# ScaleSimulator_Test.net
KiCad netlist of a schematic drawn in Altium Designer
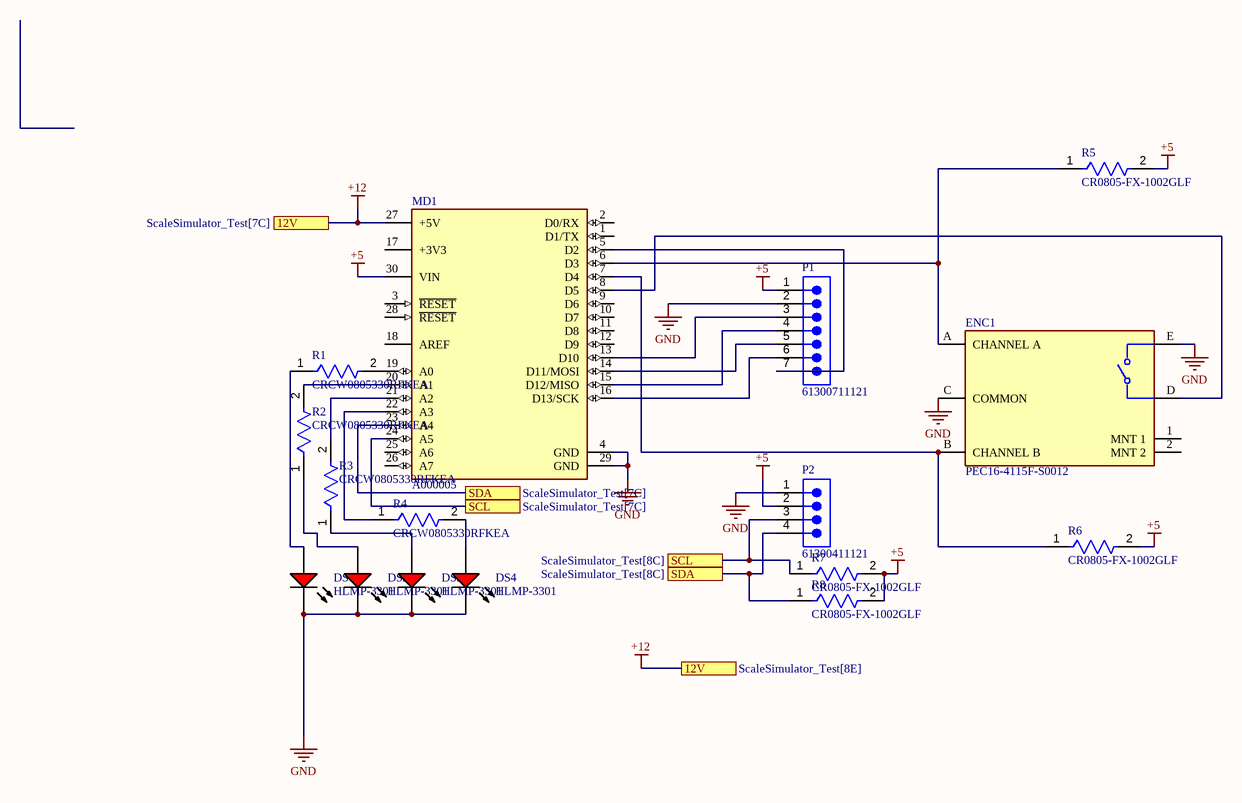
[diagram p0: ScaleSimulator_Test.SchDoc]

(export (version "E")
  (design (tool "Eeschema 10.0.6"))
  (components
    (comp (ref "DS1")
      (value "HLMP-3301")
      (footprint "AVAG-HLMP-3301-2")
      (description "T-1 3/4 (5 mm) Diffused LED Lamp, 1.9 V, -40 to 100 degC, 2-Pin THD, RoHS, Bulk")
      (fields (field (name "MANUFACTURER") "Avago"))
      (libsource (lib "Altium Content Vault") (part "LED-RED-K1A2-2"))
    )
    (comp (ref "DS2")
      (value "HLMP-3301")
      (footprint "AVAG-HLMP-3301-2")
      (description "T-1 3/4 (5 mm) Diffused LED Lamp, 1.9 V, -40 to 100 degC, 2-Pin THD, RoHS, Bulk")
      (fields (field (name "MANUFACTURER") "Avago"))
      (libsource (lib "Altium Content Vault") (part "LED-RED-K1A2-2"))
    )
    (comp (ref "DS3")
      (value "HLMP-3301")
      (footprint "AVAG-HLMP-3301-2")
      (description "T-1 3/4 (5 mm) Diffused LED Lamp, 1.9 V, -40 to 100 degC, 2-Pin THD, RoHS, Bulk")
      (fields (field (name "MANUFACTURER") "Avago"))
      (libsource (lib "Altium Content Vault") (part "LED-RED-K1A2-2"))
    )
    (comp (ref "DS4")
      (value "HLMP-3301")
      (footprint "AVAG-HLMP-3301-2")
      (description "T-1 3/4 (5 mm) Diffused LED Lamp, 1.9 V, -40 to 100 degC, 2-Pin THD, RoHS, Bulk")
      (fields (field (name "MANUFACTURER") "Avago"))
      (libsource (lib "Altium Content Vault") (part "LED-RED-K1A2-2"))
    )
    (comp (ref "ENC1")
      (value "PEC16-4115F-S0012")
      (footprint "FP-PEC16-4115F-S0012-MFG")
      (description "ROTARY ENCODER MECHANICAL 12PPR")
      (libsource (lib "Altium Content Vault") (part "74e6fcc4b0c7d654d48d7f2a48e5514"))
    )
    (comp (ref "MD1")
      (value "A000005")
      (footprint "FP-A000005-MFG")
      (description "ARDUINO NANO ATMEGA328 EVAL BRD")
      (libsource (lib "Altium Content Vault") (part "d190c066e99afd1c6882cf92e11b2cc"))
    )
    (comp (ref "P1")
      (value "61300711121")
      (footprint "61300711121")
      (libsource (lib "Altium Content Vault") (part "Header_Male_1R_07P"))
    )
    (comp (ref "P2")
      (value "61300411121")
      (footprint "61300411121")
      (libsource (lib "Altium Content Vault") (part "Header_Male_1R_04P"))
    )
    (comp (ref "R1")
      (value "CRCW0805330RFKEA")
      (footprint "FP-CRCW0805-e3-MFG")
      (description "RES Thick Film, 330Ω, 1%, 0.125W, 100ppm/°C, 0805")
      (fields (field (name "TOLERANCE") "1%"))
      (libsource (lib "Altium Content Vault") (part "1029c3af85768c4190bb7ad29bc67b5"))
    )
    (comp (ref "R2")
      (value "CRCW0805330RFKEA")
      (footprint "FP-CRCW0805-e3-MFG")
      (description "RES Thick Film, 330Ω, 1%, 0.125W, 100ppm/°C, 0805")
      (fields (field (name "TOLERANCE") "1%"))
      (libsource (lib "Altium Content Vault") (part "1029c3af85768c4190bb7ad29bc67b5"))
    )
    (comp (ref "R3")
      (value "CRCW0805330RFKEA")
      (footprint "FP-CRCW0805-e3-MFG")
      (description "RES Thick Film, 330Ω, 1%, 0.125W, 100ppm/°C, 0805")
      (fields (field (name "TOLERANCE") "1%"))
      (libsource (lib "Altium Content Vault") (part "1029c3af85768c4190bb7ad29bc67b5"))
    )
    (comp (ref "R4")
      (value "CRCW0805330RFKEA")
      (footprint "FP-CRCW0805-e3-MFG")
      (description "RES Thick Film, 330Ω, 1%, 0.125W, 100ppm/°C, 0805")
      (fields (field (name "TOLERANCE") "1%"))
      (libsource (lib "Altium Content Vault") (part "1029c3af85768c4190bb7ad29bc67b5"))
    )
    (comp (ref "R5")
      (value "CR0805-FX-1002GLF")
      (footprint "FP-CR0805-IPC_C")
      (description "Thick Film Chip Resistors 0805 10kΩ 0.125W 1% 100ppm/°C")
      (fields (field (name "TOLERANCE") "1%"))
      (libsource (lib "Altium Content Vault") (part "1029c3af85768c4190bb7ad29bc67b5"))
    )
    (comp (ref "R6")
      (value "CR0805-FX-1002GLF")
      (footprint "FP-CR0805-IPC_C")
      (description "Thick Film Chip Resistors 0805 10kΩ 0.125W 1% 100ppm/°C")
      (fields (field (name "TOLERANCE") "1%"))
      (libsource (lib "Altium Content Vault") (part "1029c3af85768c4190bb7ad29bc67b5"))
    )
    (comp (ref "R7")
      (value "CR0805-FX-1002GLF")
      (footprint "FP-CR0805-IPC_C")
      (description "Thick Film Chip Resistors 0805 10kΩ 0.125W 1% 100ppm/°C")
      (fields (field (name "TOLERANCE") "1%"))
      (libsource (lib "Altium Content Vault") (part "1029c3af85768c4190bb7ad29bc67b5"))
    )
    (comp (ref "R8")
      (value "CR0805-FX-1002GLF")
      (footprint "FP-CR0805-IPC_C")
      (description "Thick Film Chip Resistors 0805 10kΩ 0.125W 1% 100ppm/°C")
      (fields (field (name "TOLERANCE") "1%"))
      (libsource (lib "Altium Content Vault") (part "1029c3af85768c4190bb7ad29bc67b5"))
    )
  )
  (nets
    (net (code "1") (name "+5") (class "Default")
      (node (ref "MD1") (pin "30") (pinfunction "VIN_30") (pintype "power_in"))
      (node (ref "P1") (pin "1") (pinfunction "1_1") (pintype "passive"))
      (node (ref "P2") (pin "2") (pinfunction "2_2") (pintype "passive"))
      (node (ref "R5") (pin "2") (pinfunction "2_2") (pintype "passive"))
      (node (ref "R6") (pin "2") (pinfunction "2_2") (pintype "passive"))
      (node (ref "R7") (pin "2") (pinfunction "2_2") (pintype "passive"))
      (node (ref "R8") (pin "2") (pinfunction "2_2") (pintype "passive"))
    )
    (net (code "2") (name "+12") (class "Default")
      (node (ref "MD1") (pin "27") (pinfunction "+5V_27") (pintype "power_in"))
    )
    (net (code "3") (name "/SCL") (class "Default")
      (node (ref "MD1") (pin "24") (pinfunction "A5_24") (pintype "bidirectional"))
      (node (ref "P2") (pin "3") (pinfunction "3_3") (pintype "passive"))
      (node (ref "R7") (pin "1") (pinfunction "1_1") (pintype "passive"))
    )
    (net (code "4") (name "/SDA") (class "Default")
      (node (ref "MD1") (pin "23") (pinfunction "A4_23") (pintype "bidirectional"))
      (node (ref "P2") (pin "4") (pinfunction "4_4") (pintype "passive"))
      (node (ref "R8") (pin "1") (pinfunction "1_1") (pintype "passive"))
    )
    (net (code "5") (name "GND") (class "Default")
      (node (ref "DS1") (pin "1") (pinfunction "K_1") (pintype "passive"))
      (node (ref "DS2") (pin "1") (pinfunction "K_1") (pintype "passive"))
      (node (ref "DS3") (pin "1") (pinfunction "K_1") (pintype "passive"))
      (node (ref "DS4") (pin "1") (pinfunction "K_1") (pintype "passive"))
      (node (ref "ENC1") (pin "C") (pinfunction "COMMON_C") (pintype "passive"))
      (node (ref "ENC1") (pin "E") (pinfunction "E_E") (pintype "passive"))
      (node (ref "MD1") (pin "29") (pinfunction "GND_29") (pintype "power_in"))
      (node (ref "MD1") (pin "4") (pinfunction "GND_4") (pintype "power_in"))
      (node (ref "P1") (pin "2") (pinfunction "2_2") (pintype "passive"))
      (node (ref "P2") (pin "1") (pinfunction "1_1") (pintype "passive"))
    )
    (net (code "6") (name "Net-(DS1-A)") (class "Default")
      (node (ref "DS1") (pin "2") (pinfunction "A_2") (pintype "passive"))
      (node (ref "R1") (pin "1") (pinfunction "1_1") (pintype "passive"))
    )
    (net (code "7") (name "Net-(DS2-A)") (class "Default")
      (node (ref "DS2") (pin "2") (pinfunction "A_2") (pintype "passive"))
      (node (ref "R2") (pin "1") (pinfunction "1_1") (pintype "passive"))
    )
    (net (code "8") (name "Net-(DS3-A)") (class "Default")
      (node (ref "DS3") (pin "2") (pinfunction "A_2") (pintype "passive"))
      (node (ref "R3") (pin "1") (pinfunction "1_1") (pintype "passive"))
    )
    (net (code "9") (name "Net-(DS4-A)") (class "Default")
      (node (ref "DS4") (pin "2") (pinfunction "A_2") (pintype "passive"))
      (node (ref "R4") (pin "2") (pinfunction "2_2") (pintype "passive"))
    )
    (net (code "10") (name "Net-(ENC1-CHANNEL_A)") (class "Default")
      (node (ref "ENC1") (pin "A") (pinfunction "CHANNEL_A_A") (pintype "passive"))
      (node (ref "MD1") (pin "6") (pinfunction "D3_6") (pintype "bidirectional"))
      (node (ref "R5") (pin "1") (pinfunction "1_1") (pintype "passive"))
    )
    (net (code "11") (name "Net-(ENC1-CHANNEL_B)") (class "Default")
      (node (ref "ENC1") (pin "B") (pinfunction "CHANNEL_B_B") (pintype "passive"))
      (node (ref "MD1") (pin "7") (pinfunction "D4_7") (pintype "bidirectional"))
      (node (ref "R6") (pin "1") (pinfunction "1_1") (pintype "passive"))
    )
    (net (code "12") (name "Net-(MD1-A0)") (class "Default")
      (node (ref "MD1") (pin "19") (pinfunction "A0_19") (pintype "bidirectional"))
      (node (ref "R1") (pin "2") (pinfunction "2_2") (pintype "passive"))
    )
    (net (code "13") (name "Net-(MD1-A1)") (class "Default")
      (node (ref "MD1") (pin "20") (pinfunction "A1_20") (pintype "bidirectional"))
      (node (ref "R2") (pin "2") (pinfunction "2_2") (pintype "passive"))
    )
    (net (code "14") (name "Net-(MD1-A2)") (class "Default")
      (node (ref "MD1") (pin "21") (pinfunction "A2_21") (pintype "bidirectional"))
      (node (ref "R3") (pin "2") (pinfunction "2_2") (pintype "passive"))
    )
    (net (code "15") (name "Net-(MD1-A3)") (class "Default")
      (node (ref "MD1") (pin "22") (pinfunction "A3_22") (pintype "bidirectional"))
      (node (ref "R4") (pin "1") (pinfunction "1_1") (pintype "passive"))
    )
    (net (code "16") (name "Net-(MD1-D2)") (class "Default")
      (node (ref "MD1") (pin "5") (pinfunction "D2_5") (pintype "bidirectional"))
      (node (ref "P1") (pin "7") (pinfunction "7_7") (pintype "passive"))
    )
    (net (code "17") (name "Net-(MD1-D5)") (class "Default")
      (node (ref "ENC1") (pin "D") (pinfunction "D_D") (pintype "passive"))
      (node (ref "MD1") (pin "8") (pinfunction "D5_8") (pintype "bidirectional"))
    )
    (net (code "18") (name "Net-(MD1-D10)") (class "Default")
      (node (ref "MD1") (pin "13") (pinfunction "D10_13") (pintype "bidirectional"))
      (node (ref "P1") (pin "3") (pinfunction "3_3") (pintype "passive"))
    )
    (net (code "19") (name "Net-(MD1-D11{slash}MOSI)") (class "Default")
      (node (ref "MD1") (pin "14") (pinfunction "D11/MOSI_14") (pintype "bidirectional"))
      (node (ref "P1") (pin "5") (pinfunction "5_5") (pintype "passive"))
    )
    (net (code "20") (name "Net-(MD1-D12{slash}MISO)") (class "Default")
      (node (ref "MD1") (pin "15") (pinfunction "D12/MISO_15") (pintype "bidirectional"))
      (node (ref "P1") (pin "4") (pinfunction "4_4") (pintype "passive"))
    )
    (net (code "21") (name "Net-(MD1-D13{slash}SCK)") (class "Default")
      (node (ref "MD1") (pin "16") (pinfunction "D13/SCK_16") (pintype "bidirectional"))
      (node (ref "P1") (pin "6") (pinfunction "6_6") (pintype "passive"))
    )
    (net (code "22") (name "unconnected-(ENC1-MNT_1-Pad1)") (class "Default")
      (node (ref "ENC1") (pin "1") (pinfunction "MNT_1_1") (pintype "passive"))
    )
    (net (code "23") (name "unconnected-(ENC1-MNT_2-Pad2)") (class "Default")
      (node (ref "ENC1") (pin "2") (pinfunction "MNT_2_2") (pintype "passive"))
    )
    (net (code "24") (name "unconnected-(MD1-+3V3-Pad17)") (class "Default")
      (node (ref "MD1") (pin "17") (pinfunction "+3V3_17") (pintype "power_in"))
    )
    (net (code "25") (name "unconnected-(MD1-A6-Pad25)") (class "Default")
      (node (ref "MD1") (pin "25") (pinfunction "A6_25") (pintype "bidirectional"))
    )
    (net (code "26") (name "unconnected-(MD1-A7-Pad26)") (class "Default")
      (node (ref "MD1") (pin "26") (pinfunction "A7_26") (pintype "bidirectional"))
    )
    (net (code "27") (name "unconnected-(MD1-AREF-Pad18)") (class "Default")
      (node (ref "MD1") (pin "18") (pinfunction "AREF_18") (pintype "passive"))
    )
    (net (code "28") (name "unconnected-(MD1-D0{slash}RX-Pad2)") (class "Default")
      (node (ref "MD1") (pin "2") (pinfunction "D0/RX_2") (pintype "bidirectional"))
    )
    (net (code "29") (name "unconnected-(MD1-D1{slash}TX-Pad1)") (class "Default")
      (node (ref "MD1") (pin "1") (pinfunction "D1/TX_1") (pintype "bidirectional"))
    )
    (net (code "30") (name "unconnected-(MD1-D6-Pad9)") (class "Default")
      (node (ref "MD1") (pin "9") (pinfunction "D6_9") (pintype "bidirectional"))
    )
    (net (code "31") (name "unconnected-(MD1-D7-Pad10)") (class "Default")
      (node (ref "MD1") (pin "10") (pinfunction "D7_10") (pintype "bidirectional"))
    )
    (net (code "32") (name "unconnected-(MD1-D8-Pad11)") (class "Default")
      (node (ref "MD1") (pin "11") (pinfunction "D8_11") (pintype "bidirectional"))
    )
    (net (code "33") (name "unconnected-(MD1-D9-Pad12)") (class "Default")
      (node (ref "MD1") (pin "12") (pinfunction "D9_12") (pintype "bidirectional"))
    )
    (net (code "34") (name "unconnected-(MD1-~{RESET}-Pad3)") (class "Default")
      (node (ref "MD1") (pin "3") (pinfunction "~{RESET}_3") (pintype "input"))
    )
    (net (code "35") (name "unconnected-(MD1-~{RESET}-Pad28)") (class "Default")
      (node (ref "MD1") (pin "28") (pinfunction "~{RESET}_28") (pintype "input"))
    )
  )
)
